# Vcc_GndConnected.net
KiCad netlist of a schematic drawn in EAGLE
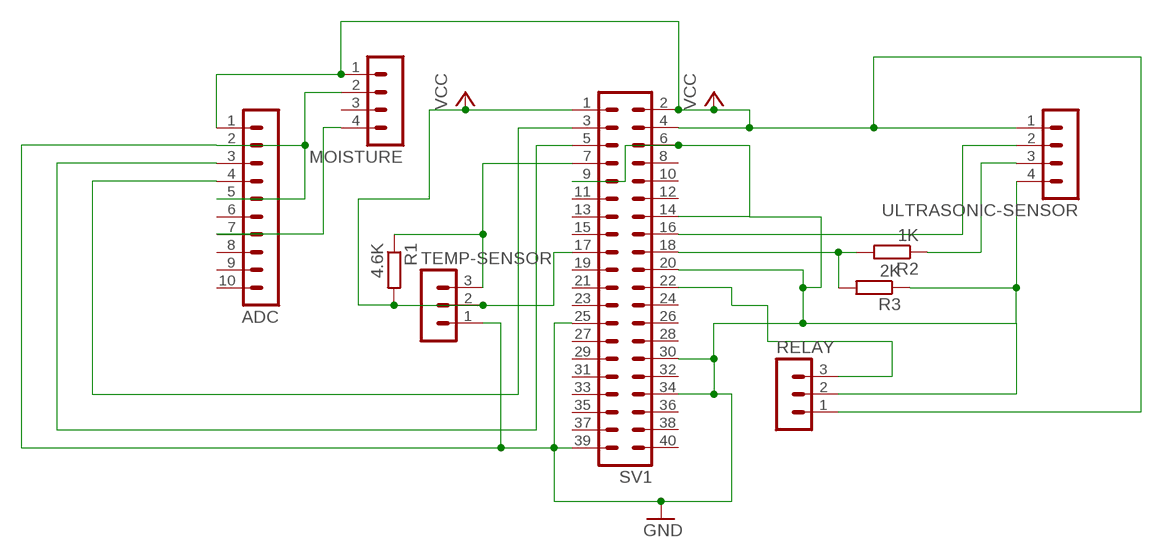
[diagram p0: schematic, sheet 1]

(export (version "E")
  (design (tool "Eeschema 10.0.6"))
  (components
    (comp (ref "ADC")
      (value "MA10-1")
      (footprint "eagle-import:MA10-1")
      (libsource (lib "eagle-import") (part "MA10-1"))
    )
    (comp (ref "MOISTURE")
      (value "MA04-1")
      (footprint "eagle-import:MA04-1")
      (libsource (lib "eagle-import") (part "MA04-1"))
    )
    (comp (ref "R1")
      (value "4.6K")
      (footprint "eagle-import:0207_10")
      (libsource (lib "eagle-import") (part "R-EU_0207/10"))
    )
    (comp (ref "R2")
      (value "1K")
      (footprint "eagle-import:0207_10")
      (libsource (lib "eagle-import") (part "R-EU_0207/10"))
    )
    (comp (ref "R3")
      (value "2K")
      (footprint "eagle-import:0207_10")
      (libsource (lib "eagle-import") (part "R-EU_0207/10"))
    )
    (comp (ref "RELAY")
      (value "MA03-1")
      (footprint "eagle-import:MA03-1")
      (libsource (lib "eagle-import") (part "MA03-1"))
    )
    (comp (ref "SV1")
      (value "MA20-2")
      (footprint "eagle-import:MA20-2")
      (libsource (lib "eagle-import") (part "MA20-2"))
    )
    (comp (ref "TEMP-SENSOR")
      (value "MA03-1")
      (footprint "eagle-import:MA03-1")
      (libsource (lib "eagle-import") (part "MA03-1"))
    )
    (comp (ref "ULTRASONIC-SENSOR")
      (value "MA04-1")
      (footprint "eagle-import:MA04-1")
      (libsource (lib "eagle-import") (part "MA04-1"))
    )
  )
  (nets
    (net (code "1") (name "GND") (class "Default")
      (node (ref "ADC") (pin "2") (pinfunction "2_2") (pintype "passive"))
      (node (ref "ADC") (pin "5") (pinfunction "5_5") (pintype "passive"))
      (node (ref "MOISTURE") (pin "2") (pinfunction "2_2") (pintype "passive"))
      (node (ref "R3") (pin "1") (pinfunction "1_1") (pintype "passive"))
      (node (ref "RELAY") (pin "2") (pinfunction "2_2") (pintype "passive"))
      (node (ref "SV1") (pin "14") (pinfunction "14_14") (pintype "passive"))
      (node (ref "SV1") (pin "20") (pinfunction "20_20") (pintype "passive"))
      (node (ref "SV1") (pin "25") (pinfunction "25_25") (pintype "passive"))
      (node (ref "SV1") (pin "30") (pinfunction "30_30") (pintype "passive"))
      (node (ref "SV1") (pin "34") (pinfunction "34_34") (pintype "passive"))
      (node (ref "SV1") (pin "39") (pinfunction "39_39") (pintype "passive"))
      (node (ref "SV1") (pin "6") (pinfunction "6_6") (pintype "passive"))
      (node (ref "SV1") (pin "9") (pinfunction "9_9") (pintype "passive"))
      (node (ref "TEMP-SENSOR") (pin "1") (pinfunction "1_1") (pintype "passive"))
      (node (ref "ULTRASONIC-SENSOR") (pin "4") (pinfunction "4_4") (pintype "passive"))
    )
    (net (code "2") (name "Net-(ADC-Pad3)") (class "Default")
      (node (ref "ADC") (pin "3") (pinfunction "3_3") (pintype "passive"))
      (node (ref "SV1") (pin "5") (pinfunction "5_5") (pintype "passive"))
    )
    (net (code "3") (name "Net-(ADC-Pad4)") (class "Default")
      (node (ref "ADC") (pin "4") (pinfunction "4_4") (pintype "passive"))
      (node (ref "SV1") (pin "3") (pinfunction "3_3") (pintype "passive"))
    )
    (net (code "4") (name "Net-(ADC-Pad7)") (class "Default")
      (node (ref "ADC") (pin "7") (pinfunction "7_7") (pintype "passive"))
      (node (ref "MOISTURE") (pin "4") (pinfunction "4_4") (pintype "passive"))
    )
    (net (code "5") (name "Net-(R1-Pad1)") (class "Default")
      (node (ref "R1") (pin "1") (pinfunction "1_1") (pintype "passive"))
      (node (ref "SV1") (pin "7") (pinfunction "7_7") (pintype "passive"))
      (node (ref "TEMP-SENSOR") (pin "3") (pinfunction "3_3") (pintype "passive"))
    )
    (net (code "6") (name "Net-(R2-Pad1)") (class "Default")
      (node (ref "R2") (pin "1") (pinfunction "1_1") (pintype "passive"))
      (node (ref "ULTRASONIC-SENSOR") (pin "3") (pinfunction "3_3") (pintype "passive"))
    )
    (net (code "7") (name "Net-(R2-Pad2)") (class "Default")
      (node (ref "R2") (pin "2") (pinfunction "2_2") (pintype "passive"))
      (node (ref "R3") (pin "2") (pinfunction "2_2") (pintype "passive"))
      (node (ref "SV1") (pin "18") (pinfunction "18_18") (pintype "passive"))
    )
    (net (code "8") (name "Net-(RELAY-Pad3)") (class "Default")
      (node (ref "RELAY") (pin "3") (pinfunction "3_3") (pintype "passive"))
      (node (ref "SV1") (pin "22") (pinfunction "22_22") (pintype "passive"))
    )
    (net (code "9") (name "Net-(SV1-Pad16)") (class "Default")
      (node (ref "SV1") (pin "16") (pinfunction "16_16") (pintype "passive"))
      (node (ref "ULTRASONIC-SENSOR") (pin "2") (pinfunction "2_2") (pintype "passive"))
    )
    (net (code "10") (name "VCC") (class "Default")
      (node (ref "ADC") (pin "1") (pinfunction "1_1") (pintype "passive"))
      (node (ref "MOISTURE") (pin "1") (pinfunction "1_1") (pintype "passive"))
      (node (ref "R1") (pin "2") (pinfunction "2_2") (pintype "passive"))
      (node (ref "RELAY") (pin "1") (pinfunction "1_1") (pintype "passive"))
      (node (ref "SV1") (pin "1") (pinfunction "1_1") (pintype "passive"))
      (node (ref "SV1") (pin "17") (pinfunction "17_17") (pintype "passive"))
      (node (ref "SV1") (pin "2") (pinfunction "2_2") (pintype "passive"))
      (node (ref "SV1") (pin "4") (pinfunction "4_4") (pintype "passive"))
      (node (ref "TEMP-SENSOR") (pin "2") (pinfunction "2_2") (pintype "passive"))
      (node (ref "ULTRASONIC-SENSOR") (pin "1") (pinfunction "1_1") (pintype "passive"))
    )
    (net (code "11") (name "unconnected-(ADC-Pad6)") (class "Default")
      (node (ref "ADC") (pin "6") (pinfunction "6_6") (pintype "passive"))
    )
    (net (code "12") (name "unconnected-(ADC-Pad8)") (class "Default")
      (node (ref "ADC") (pin "8") (pinfunction "8_8") (pintype "passive"))
    )
    (net (code "13") (name "unconnected-(ADC-Pad9)") (class "Default")
      (node (ref "ADC") (pin "9") (pinfunction "9_9") (pintype "passive"))
    )
    (net (code "14") (name "unconnected-(ADC-Pad10)") (class "Default")
      (node (ref "ADC") (pin "10") (pinfunction "10_10") (pintype "passive"))
    )
    (net (code "15") (name "unconnected-(MOISTURE-Pad3)") (class "Default")
      (node (ref "MOISTURE") (pin "3") (pinfunction "3_3") (pintype "passive"))
    )
    (net (code "16") (name "unconnected-(SV1-Pad8)") (class "Default")
      (node (ref "SV1") (pin "8") (pinfunction "8_8") (pintype "passive"))
    )
    (net (code "17") (name "unconnected-(SV1-Pad10)") (class "Default")
      (node (ref "SV1") (pin "10") (pinfunction "10_10") (pintype "passive"))
    )
    (net (code "18") (name "unconnected-(SV1-Pad11)") (class "Default")
      (node (ref "SV1") (pin "11") (pinfunction "11_11") (pintype "passive"))
    )
    (net (code "19") (name "unconnected-(SV1-Pad12)") (class "Default")
      (node (ref "SV1") (pin "12") (pinfunction "12_12") (pintype "passive"))
    )
    (net (code "20") (name "unconnected-(SV1-Pad13)") (class "Default")
      (node (ref "SV1") (pin "13") (pinfunction "13_13") (pintype "passive"))
    )
    (net (code "21") (name "unconnected-(SV1-Pad15)") (class "Default")
      (node (ref "SV1") (pin "15") (pinfunction "15_15") (pintype "passive"))
    )
    (net (code "22") (name "unconnected-(SV1-Pad19)") (class "Default")
      (node (ref "SV1") (pin "19") (pinfunction "19_19") (pintype "passive"))
    )
    (net (code "23") (name "unconnected-(SV1-Pad21)") (class "Default")
      (node (ref "SV1") (pin "21") (pinfunction "21_21") (pintype "passive"))
    )
    (net (code "24") (name "unconnected-(SV1-Pad23)") (class "Default")
      (node (ref "SV1") (pin "23") (pinfunction "23_23") (pintype "passive"))
    )
    (net (code "25") (name "unconnected-(SV1-Pad24)") (class "Default")
      (node (ref "SV1") (pin "24") (pinfunction "24_24") (pintype "passive"))
    )
    (net (code "26") (name "unconnected-(SV1-Pad26)") (class "Default")
      (node (ref "SV1") (pin "26") (pinfunction "26_26") (pintype "passive"))
    )
    (net (code "27") (name "unconnected-(SV1-Pad27)") (class "Default")
      (node (ref "SV1") (pin "27") (pinfunction "27_27") (pintype "passive"))
    )
    (net (code "28") (name "unconnected-(SV1-Pad28)") (class "Default")
      (node (ref "SV1") (pin "28") (pinfunction "28_28") (pintype "passive"))
    )
    (net (code "29") (name "unconnected-(SV1-Pad29)") (class "Default")
      (node (ref "SV1") (pin "29") (pinfunction "29_29") (pintype "passive"))
    )
    (net (code "30") (name "unconnected-(SV1-Pad31)") (class "Default")
      (node (ref "SV1") (pin "31") (pinfunction "31_31") (pintype "passive"))
    )
    (net (code "31") (name "unconnected-(SV1-Pad32)") (class "Default")
      (node (ref "SV1") (pin "32") (pinfunction "32_32") (pintype "passive"))
    )
    (net (code "32") (name "unconnected-(SV1-Pad33)") (class "Default")
      (node (ref "SV1") (pin "33") (pinfunction "33_33") (pintype "passive"))
    )
    (net (code "33") (name "unconnected-(SV1-Pad35)") (class "Default")
      (node (ref "SV1") (pin "35") (pinfunction "35_35") (pintype "passive"))
    )
    (net (code "34") (name "unconnected-(SV1-Pad36)") (class "Default")
      (node (ref "SV1") (pin "36") (pinfunction "36_36") (pintype "passive"))
    )
    (net (code "35") (name "unconnected-(SV1-Pad37)") (class "Default")
      (node (ref "SV1") (pin "37") (pinfunction "37_37") (pintype "passive"))
    )
    (net (code "36") (name "unconnected-(SV1-Pad38)") (class "Default")
      (node (ref "SV1") (pin "38") (pinfunction "38_38") (pintype "passive"))
    )
    (net (code "37") (name "unconnected-(SV1-Pad40)") (class "Default")
      (node (ref "SV1") (pin "40") (pinfunction "40_40") (pintype "passive"))
    )
  )
)
